# pa_blank.net
KiCad netlist of a schematic drawn in Altium Designer
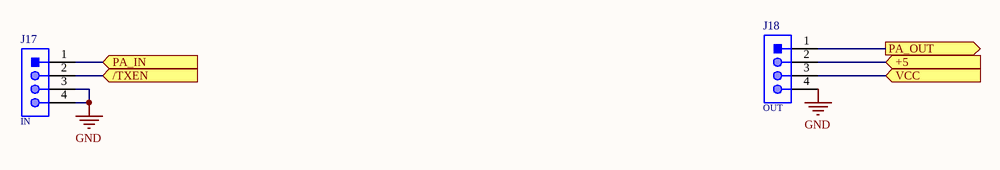
[diagram p0: pa_blank.SchDoc]

(export (version "E")
  (design (tool "Eeschema 10.0.6"))
  (components
    (comp (ref "J17")
      (value "IN")
      (footprint "61300411121")
      (description "THT Vertical Pin Header WR-PHD, Pitch 2.54 mm, Single Row, 4 pins")
      (fields
        (field (name "MANUFACTURER") "Wurth Elektronik")
        (field (name "PART NUMBER") "61300411121")
        (field (name "PUBLISHER") "WurthElektronik")
      )
      (libsource (lib "Altium Content Vault") (part "WE-CN-1P-M-R4"))
    )
    (comp (ref "J18")
      (value "OUT")
      (footprint "61300411121")
      (description "THT Vertical Pin Header WR-PHD, Pitch 2.54 mm, Single Row, 4 pins")
      (fields
        (field (name "MANUFACTURER") "Wurth Elektronik")
        (field (name "PART NUMBER") "61300411121")
        (field (name "PUBLISHER") "WurthElektronik")
      )
      (libsource (lib "Altium Content Vault") (part "WE-CN-1P-M-R4"))
    )
  )
  (nets
    (net (code "1") (name "/+5") (class "Default")
      (node (ref "J18") (pin "2") (pinfunction "2_2") (pintype "passive"))
    )
    (net (code "2") (name "/PA_IN") (class "Default")
      (node (ref "J17") (pin "1") (pinfunction "1_1") (pintype "passive"))
    )
    (net (code "3") (name "/PA_OUT") (class "Default")
      (node (ref "J18") (pin "1") (pinfunction "1_1") (pintype "passive"))
    )
    (net (code "4") (name "/VCC") (class "Default")
      (node (ref "J18") (pin "3") (pinfunction "3_3") (pintype "passive"))
    )
    (net (code "5") (name "/{slash}TXEN") (class "Default")
      (node (ref "J17") (pin "2") (pinfunction "2_2") (pintype "passive"))
    )
    (net (code "6") (name "GND") (class "Default")
      (node (ref "J17") (pin "3") (pinfunction "3_3") (pintype "passive"))
      (node (ref "J17") (pin "4") (pinfunction "4_4") (pintype "passive"))
      (node (ref "J18") (pin "4") (pinfunction "4_4") (pintype "passive"))
    )
  )
)
